# valve_board.net
KiCad netlist of a schematic drawn in EAGLE
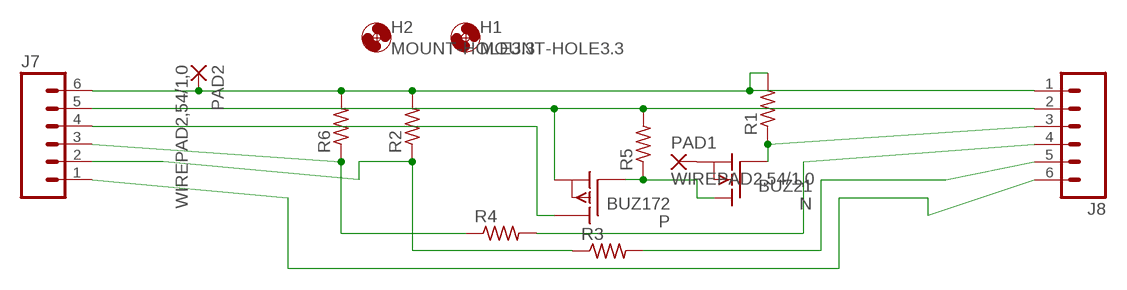
[diagram p0: schematic, sheet 1]

(export (version "E")
  (design (tool "Eeschema 10.0.6"))
  (components
    (comp (ref "H1")
      (value "MOUNT-HOLE3.3")
      (footprint "eagle-import:3,3")
      (libsource (lib "eagle-import") (part "MOUNT-HOLE3.3"))
    )
    (comp (ref "H2")
      (value "MOUNT-HOLE3.3")
      (footprint "eagle-import:3,3")
      (libsource (lib "eagle-import") (part "MOUNT-HOLE3.3"))
    )
    (comp (ref "J7")
      (value "M06LOCK_LONGPADS")
      (footprint "eagle-import:1X06_LOCK_LONGPADS")
      (libsource (lib "eagle-import") (part "M06LOCK_LONGPADS"))
    )
    (comp (ref "J8")
      (value "M06LOCK_LONGPADS")
      (footprint "eagle-import:1X06_LOCK_LONGPADS")
      (libsource (lib "eagle-import") (part "M06LOCK_LONGPADS"))
    )
    (comp (ref "N")
      (value "BUZ21")
      (footprint "eagle-import:TO220")
      (libsource (lib "eagle-import") (part "BUZ21"))
    )
    (comp (ref "P")
      (value "BUZ172")
      (footprint "eagle-import:TO220")
      (libsource (lib "eagle-import") (part "BUZ172"))
    )
    (comp (ref "PAD1")
      (value "WIREPAD2,54/1,0")
      (footprint "eagle-import:2,54_1,0")
      (libsource (lib "eagle-import") (part "WIREPAD2,54/1,0"))
    )
    (comp (ref "PAD2")
      (value "WIREPAD2,54/1,0")
      (footprint "eagle-import:2,54_1,0")
      (libsource (lib "eagle-import") (part "WIREPAD2,54/1,0"))
    )
    (comp (ref "R1")
      (value "R-US_0207/10")
      (footprint "eagle-import:0207_10")
      (libsource (lib "eagle-import") (part "R-US_0207/10"))
    )
    (comp (ref "R2")
      (value "R-US_0207/10")
      (footprint "eagle-import:0207_10")
      (libsource (lib "eagle-import") (part "R-US_0207/10"))
    )
    (comp (ref "R3")
      (value "R-US_0207/10")
      (footprint "eagle-import:0207_10")
      (libsource (lib "eagle-import") (part "R-US_0207/10"))
    )
    (comp (ref "R4")
      (value "R-US_0207/10")
      (footprint "eagle-import:0207_10")
      (libsource (lib "eagle-import") (part "R-US_0207/10"))
    )
    (comp (ref "R5")
      (value "R-US_0207/10")
      (footprint "eagle-import:0207_10")
      (libsource (lib "eagle-import") (part "R-US_0207/10"))
    )
    (comp (ref "R6")
      (value "R-US_0207/10")
      (footprint "eagle-import:0207_10")
      (libsource (lib "eagle-import") (part "R-US_0207/10"))
    )
  )
  (nets
    (net (code "1") (name "Net-(J7-Pad1)") (class "Default")
      (node (ref "J7") (pin "1") (pinfunction "1_1") (pintype "passive"))
      (node (ref "J8") (pin "6") (pinfunction "6_6") (pintype "passive"))
    )
    (net (code "2") (name "Net-(J7-Pad2)") (class "Default")
      (node (ref "J7") (pin "2") (pinfunction "2_2") (pintype "passive"))
      (node (ref "R2") (pin "1") (pinfunction "1_1") (pintype "passive"))
      (node (ref "R3") (pin "1") (pinfunction "1_1") (pintype "passive"))
    )
    (net (code "3") (name "Net-(J7-Pad3)") (class "Default")
      (node (ref "J7") (pin "3") (pinfunction "3_3") (pintype "passive"))
      (node (ref "R4") (pin "1") (pinfunction "1_1") (pintype "passive"))
      (node (ref "R6") (pin "1") (pinfunction "1_1") (pintype "passive"))
    )
    (net (code "4") (name "Net-(J8-Pad4)") (class "Default")
      (node (ref "J8") (pin "4") (pinfunction "4_4") (pintype "passive"))
      (node (ref "R4") (pin "2") (pinfunction "2_2") (pintype "passive"))
    )
    (net (code "5") (name "Net-(J8-Pad5)") (class "Default")
      (node (ref "J8") (pin "5") (pinfunction "5_5") (pintype "passive"))
      (node (ref "R3") (pin "2") (pinfunction "2_2") (pintype "passive"))
    )
    (net (code "6") (name "Net-(N-D)") (class "Default")
      (node (ref "N") (pin "2") (pinfunction "D_2") (pintype "passive"))
      (node (ref "P") (pin "1") (pinfunction "G_1") (pintype "passive"))
      (node (ref "R5") (pin "1") (pinfunction "1_1") (pintype "passive"))
    )
    (net (code "7") (name "Net-(N-G)") (class "Default")
      (node (ref "J8") (pin "3") (pinfunction "3_3") (pintype "passive"))
      (node (ref "N") (pin "1") (pinfunction "G_1") (pintype "passive"))
      (node (ref "R1") (pin "1") (pinfunction "1_1") (pintype "passive"))
    )
    (net (code "8") (name "Net-(N-S)") (class "Default")
      (node (ref "N") (pin "3") (pinfunction "S_3") (pintype "passive"))
      (node (ref "PAD1") (pin "1") (pinfunction "P_1") (pintype "passive"))
    )
    (net (code "9") (name "Net-(P-D)") (class "Default")
      (node (ref "J7") (pin "4") (pinfunction "4_4") (pintype "passive"))
      (node (ref "P") (pin "2") (pinfunction "D_2") (pintype "passive"))
    )
    (net (code "10") (name "Net-(P-S)") (class "Default")
      (node (ref "J7") (pin "5") (pinfunction "5_5") (pintype "passive"))
      (node (ref "J8") (pin "2") (pinfunction "2_2") (pintype "passive"))
      (node (ref "P") (pin "3") (pinfunction "S_3") (pintype "passive"))
      (node (ref "R5") (pin "2") (pinfunction "2_2") (pintype "passive"))
    )
    (net (code "11") (name "Net-(PAD2-P)") (class "Default")
      (node (ref "J7") (pin "6") (pinfunction "6_6") (pintype "passive"))
      (node (ref "J8") (pin "1") (pinfunction "1_1") (pintype "passive"))
      (node (ref "PAD2") (pin "1") (pinfunction "P_1") (pintype "passive"))
      (node (ref "R1") (pin "2") (pinfunction "2_2") (pintype "passive"))
      (node (ref "R2") (pin "2") (pinfunction "2_2") (pintype "passive"))
      (node (ref "R6") (pin "2") (pinfunction "2_2") (pintype "passive"))
    )
  )
)
